# MK_0_4.net
KiCad netlist of a schematic drawn in Altium Designer
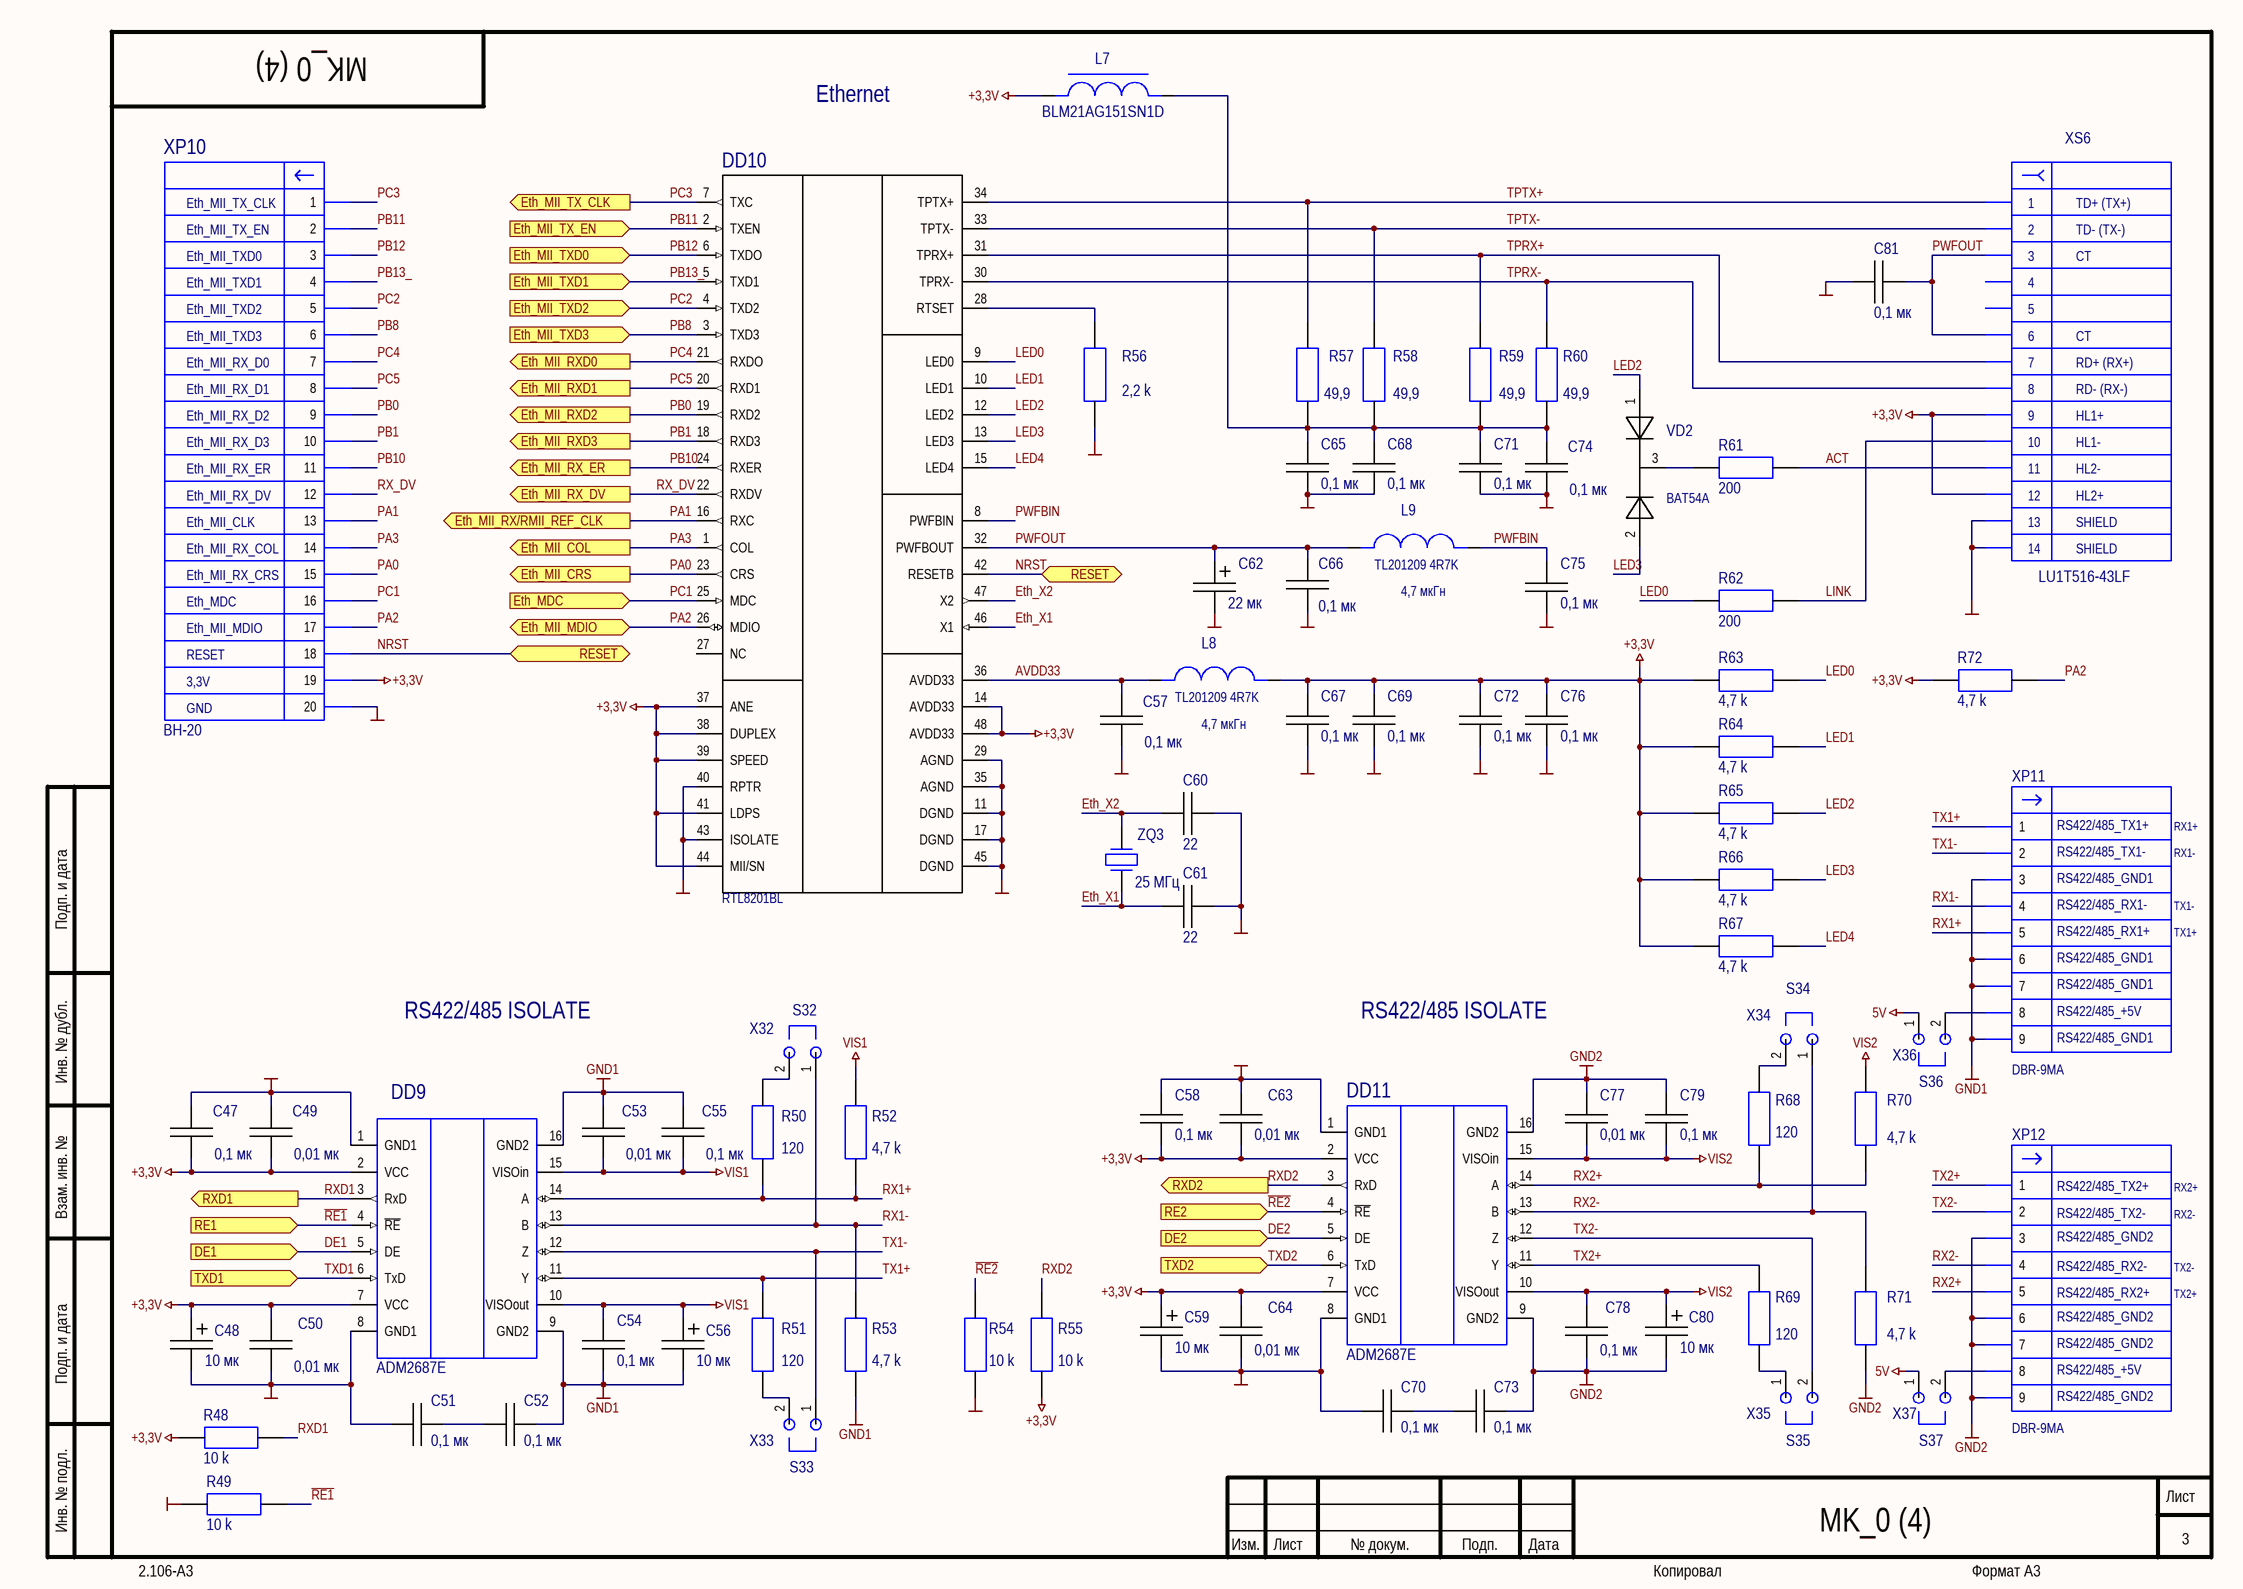
[diagram p0: MK_0 (4).SchDoc]

(export (version "E")
  (design (tool "Eeschema 10.0.6"))
  (components
    (comp (ref "C47")
      (value "0,1 мк")
      (footprint "CAPC_1206")
      (description "Capasitor")
      (fields (field (name "PART NUMBER") "C"))
      (libsource (lib "RLC_GOST") (part "C"))
    )
    (comp (ref "C48")
      (value "10 мк")
      (footprint "3216")
      (description "Capasitor_polar")
      (fields (field (name "PART NUMBER") "CapPol"))
      (libsource (lib "RLC_GOST") (part "CapPol"))
    )
    (comp (ref "C49")
      (value "0,01 мк")
      (footprint "CAPC_1206")
      (description "Capasitor")
      (fields (field (name "PART NUMBER") "C"))
      (libsource (lib "RLC_GOST") (part "C"))
    )
    (comp (ref "C50")
      (value "0,01 мк")
      (footprint "CAPC_1206")
      (description "Capasitor")
      (fields (field (name "PART NUMBER") "C"))
      (libsource (lib "RLC_GOST") (part "C"))
    )
    (comp (ref "C51")
      (value "0,1 мк")
      (footprint "CAPC_1206")
      (description "Capasitor")
      (fields (field (name "PART NUMBER") "C"))
      (libsource (lib "RLC_GOST") (part "C"))
    )
    (comp (ref "C52")
      (value "0,1 мк")
      (footprint "CAPC_1206")
      (description "Capasitor")
      (fields (field (name "PART NUMBER") "C"))
      (libsource (lib "RLC_GOST") (part "C"))
    )
    (comp (ref "C53")
      (value "0,01 мк")
      (footprint "CAPC_1206")
      (description "Capasitor")
      (fields (field (name "PART NUMBER") "C"))
      (libsource (lib "RLC_GOST") (part "C"))
    )
    (comp (ref "C54")
      (value "0,1 мк")
      (footprint "CAPC_1206")
      (description "Capasitor")
      (fields (field (name "PART NUMBER") "C"))
      (libsource (lib "RLC_GOST") (part "C"))
    )
    (comp (ref "C55")
      (value "0,1 мк")
      (footprint "CAPC_1206")
      (description "Capasitor")
      (fields (field (name "PART NUMBER") "C"))
      (libsource (lib "RLC_GOST") (part "C"))
    )
    (comp (ref "C56")
      (value "10 мк")
      (footprint "3216")
      (description "Capasitor_polar")
      (fields (field (name "PART NUMBER") "CapPol"))
      (libsource (lib "RLC_GOST") (part "CapPol"))
    )
    (comp (ref "C57")
      (value "0,1 мк")
      (footprint "CAPC_1206")
      (description "Capasitor")
      (fields (field (name "PART NUMBER") "C"))
      (libsource (lib "RLC_GOST") (part "C"))
    )
    (comp (ref "C58")
      (value "0,1 мк")
      (footprint "CAPC_1206")
      (description "Capasitor")
      (fields (field (name "PART NUMBER") "C"))
      (libsource (lib "RLC_GOST") (part "C"))
    )
    (comp (ref "C59")
      (value "10 мк")
      (footprint "3216")
      (description "Capasitor_polar")
      (fields (field (name "PART NUMBER") "CapPol"))
      (libsource (lib "RLC_GOST") (part "CapPol"))
    )
    (comp (ref "C60")
      (value "22")
      (footprint "CAPC_1206")
      (description "Capasitor")
      (libsource (lib "RLC_GOST") (part "C"))
    )
    (comp (ref "C61")
      (value "22")
      (footprint "CAPC_1206")
      (description "Capasitor")
      (libsource (lib "RLC_GOST") (part "C"))
    )
    (comp (ref "C62")
      (value "22 мк")
      (footprint "3216")
      (description "Capasitor_polar")
      (fields (field (name "PART NUMBER") "CapPol"))
      (libsource (lib "RLC_GOST") (part "CapPol"))
    )
    (comp (ref "C63")
      (value "0,01 мк")
      (footprint "CAPC_1206")
      (description "Capasitor")
      (fields (field (name "PART NUMBER") "C"))
      (libsource (lib "RLC_GOST") (part "C"))
    )
    (comp (ref "C64")
      (value "0,01 мк")
      (footprint "CAPC_1206")
      (description "Capasitor")
      (fields (field (name "PART NUMBER") "C"))
      (libsource (lib "RLC_GOST") (part "C"))
    )
    (comp (ref "C65")
      (value "0,1 мк")
      (footprint "CAPC_1206")
      (description "Capasitor")
      (fields (field (name "PART NUMBER") "C"))
      (libsource (lib "RLC_GOST") (part "C"))
    )
    (comp (ref "C66")
      (value "0,1 мк")
      (footprint "CAPC_1206")
      (description "Capasitor")
      (fields (field (name "PART NUMBER") "C"))
      (libsource (lib "RLC_GOST") (part "C"))
    )
    (comp (ref "C67")
      (value "0,1 мк")
      (footprint "CAPC_1206")
      (description "Capasitor")
      (fields (field (name "PART NUMBER") "C"))
      (libsource (lib "RLC_GOST") (part "C"))
    )
    (comp (ref "C68")
      (value "0,1 мк")
      (footprint "CAPC_1206")
      (description "Capasitor")
      (fields (field (name "PART NUMBER") "C"))
      (libsource (lib "RLC_GOST") (part "C"))
    )
    (comp (ref "C69")
      (value "0,1 мк")
      (footprint "CAPC_1206")
      (description "Capasitor")
      (fields (field (name "PART NUMBER") "C"))
      (libsource (lib "RLC_GOST") (part "C"))
    )
    (comp (ref "C70")
      (value "0,1 мк")
      (footprint "CAPC_1206")
      (description "Capasitor")
      (fields (field (name "PART NUMBER") "C"))
      (libsource (lib "RLC_GOST") (part "C"))
    )
    (comp (ref "C71")
      (value "0,1 мк")
      (footprint "CAPC_1206")
      (description "Capasitor")
      (fields (field (name "PART NUMBER") "C"))
      (libsource (lib "RLC_GOST") (part "C"))
    )
    (comp (ref "C72")
      (value "0,1 мк")
      (footprint "CAPC_1206")
      (description "Capasitor")
      (fields (field (name "PART NUMBER") "C"))
      (libsource (lib "RLC_GOST") (part "C"))
    )
    (comp (ref "C73")
      (value "0,1 мк")
      (footprint "CAPC_1206")
      (description "Capasitor")
      (fields (field (name "PART NUMBER") "C"))
      (libsource (lib "RLC_GOST") (part "C"))
    )
    (comp (ref "C74")
      (value "0,1 мк")
      (footprint "CAPC_1206")
      (description "Capasitor")
      (fields (field (name "PART NUMBER") "C"))
      (libsource (lib "RLC_GOST") (part "C"))
    )
    (comp (ref "C75")
      (value "0,1 мк")
      (footprint "CAPC_1206")
      (description "Capasitor")
      (fields (field (name "PART NUMBER") "C"))
      (libsource (lib "RLC_GOST") (part "C"))
    )
    (comp (ref "C76")
      (value "0,1 мк")
      (footprint "CAPC_1206")
      (description "Capasitor")
      (fields (field (name "PART NUMBER") "C"))
      (libsource (lib "RLC_GOST") (part "C"))
    )
    (comp (ref "C77")
      (value "0,01 мк")
      (footprint "CAPC_1206")
      (description "Capasitor")
      (fields (field (name "PART NUMBER") "C"))
      (libsource (lib "RLC_GOST") (part "C"))
    )
    (comp (ref "C78")
      (value "0,1 мк")
      (footprint "CAPC_1206")
      (description "Capasitor")
      (fields (field (name "PART NUMBER") "C"))
      (libsource (lib "RLC_GOST") (part "C"))
    )
    (comp (ref "C79")
      (value "0,1 мк")
      (footprint "CAPC_1206")
      (description "Capasitor")
      (fields (field (name "PART NUMBER") "C"))
      (libsource (lib "RLC_GOST") (part "C"))
    )
    (comp (ref "C80")
      (value "10 мк")
      (footprint "3216")
      (description "Capasitor_polar")
      (fields (field (name "PART NUMBER") "CapPol"))
      (libsource (lib "RLC_GOST") (part "CapPol"))
    )
    (comp (ref "C81")
      (value "0,1 мк")
      (footprint "CAPC_1206")
      (description "Capasitor")
      (fields (field (name "PART NUMBER") "C"))
      (libsource (lib "RLC_GOST") (part "C"))
    )
    (comp (ref "DD9")
      (value "ADM2687E")
      (footprint "SOIC_IC16")
      (description "RS422/RS485 transceivier 15 kV ESD Protection")
      (libsource (lib "Communication transceiver") (part "ADM2682E"))
    )
    (comp (ref "DD10")
      (value "RTL8201BL")
      (footprint "SQFP48")
      (description "Ethernet phyciever, 10/100M")
      (libsource (lib "Ethernet") (part "RTL8201BL"))
    )
    (comp (ref "DD11")
      (value "ADM2687E")
      (footprint "SOIC_IC16")
      (description "RS422/RS485 transceivier 15 kV ESD Protection")
      (libsource (lib "Communication transceiver") (part "ADM2682E"))
    )
    (comp (ref "L7")
      (value "BLM21AG151SN1D")
      (footprint "C0805")
      (description "Ferrite bead")
      (libsource (lib "RLC_GOST") (part "B"))
    )
    (comp (ref "L8")
      (value "TL201209 4R7K")
      (footprint "C0805")
      (description "Inductance")
      (fields (field (name "VALUE1") "4,7 мкГн"))
      (libsource (lib "RLC_GOST") (part "L"))
    )
    (comp (ref "L9")
      (value "TL201209 4R7K")
      (footprint "C0805")
      (description "Inductance")
      (fields (field (name "VALUE1") "4,7 мкГн"))
      (libsource (lib "RLC_GOST") (part "L"))
    )
    (comp (ref "R48")
      (value "10 k")
      (footprint "SMD_1206")
      (description "Resistor,2 Pin")
      (libsource (lib "RLC_GOST") (part "R_Gost"))
    )
    (comp (ref "R49")
      (value "10 k")
      (footprint "SMD_1206")
      (description "Resistor,2 Pin")
      (libsource (lib "RLC_GOST") (part "R_Gost"))
    )
    (comp (ref "R50")
      (value "120")
      (footprint "SMD_1206")
      (description "Resistor,2 Pin")
      (libsource (lib "RLC_GOST") (part "R_Gost"))
    )
    (comp (ref "R51")
      (value "120")
      (footprint "SMD_1206")
      (description "Resistor,2 Pin")
      (libsource (lib "RLC_GOST") (part "R_Gost"))
    )
    (comp (ref "R52")
      (value "4,7 k")
      (footprint "SMD_1206")
      (description "Resistor,2 Pin")
      (libsource (lib "RLC_GOST") (part "R_Gost"))
    )
    (comp (ref "R53")
      (value "4,7 k")
      (footprint "SMD_1206")
      (description "Resistor,2 Pin")
      (libsource (lib "RLC_GOST") (part "R_Gost"))
    )
    (comp (ref "R54")
      (value "10 k")
      (footprint "SMD_1206")
      (description "Resistor,2 Pin")
      (libsource (lib "RLC_GOST") (part "R_Gost"))
    )
    (comp (ref "R55")
      (value "10 k")
      (footprint "SMD_1206")
      (description "Resistor,2 Pin")
      (libsource (lib "RLC_GOST") (part "R_Gost"))
    )
    (comp (ref "R56")
      (value "2,2 k")
      (footprint "SMD_1206")
      (description "Resistor,2 Pin")
      (libsource (lib "RLC_GOST") (part "R_Gost"))
    )
    (comp (ref "R57")
      (value "49,9")
      (footprint "SMD_1206")
      (description "Resistor,2 Pin")
      (libsource (lib "RLC_GOST") (part "R_Gost"))
    )
    (comp (ref "R58")
      (value "49,9")
      (footprint "SMD_1206")
      (description "Resistor,2 Pin")
      (libsource (lib "RLC_GOST") (part "R_Gost"))
    )
    (comp (ref "R59")
      (value "49,9")
      (footprint "SMD_1206")
      (description "Resistor,2 Pin")
      (libsource (lib "RLC_GOST") (part "R_Gost"))
    )
    (comp (ref "R60")
      (value "49,9")
      (footprint "SMD_1206")
      (description "Resistor,2 Pin")
      (libsource (lib "RLC_GOST") (part "R_Gost"))
    )
    (comp (ref "R61")
      (value "200")
      (footprint "SMD_1206")
      (description "Resistor,2 Pin")
      (libsource (lib "RLC_GOST") (part "R_Gost"))
    )
    (comp (ref "R62")
      (value "200")
      (footprint "SMD_1206")
      (description "Resistor,2 Pin")
      (libsource (lib "RLC_GOST") (part "R_Gost"))
    )
    (comp (ref "R63")
      (value "4,7 k")
      (footprint "SMD_1206")
      (description "Resistor,2 Pin")
      (libsource (lib "RLC_GOST") (part "R_Gost"))
    )
    (comp (ref "R64")
      (value "4,7 k")
      (footprint "SMD_1206")
      (description "Resistor,2 Pin")
      (libsource (lib "RLC_GOST") (part "R_Gost"))
    )
    (comp (ref "R65")
      (value "4,7 k")
      (footprint "SMD_1206")
      (description "Resistor,2 Pin")
      (libsource (lib "RLC_GOST") (part "R_Gost"))
    )
    (comp (ref "R66")
      (value "4,7 k")
      (footprint "SMD_1206")
      (description "Resistor,2 Pin")
      (libsource (lib "RLC_GOST") (part "R_Gost"))
    )
    (comp (ref "R67")
      (value "4,7 k")
      (footprint "SMD_1206")
      (description "Resistor,2 Pin")
      (libsource (lib "RLC_GOST") (part "R_Gost"))
    )
    (comp (ref "R68")
      (value "120")
      (footprint "SMD_1206")
      (description "Resistor,2 Pin")
      (libsource (lib "RLC_GOST") (part "R_Gost"))
    )
    (comp (ref "R69")
      (value "120")
      (footprint "SMD_1206")
      (description "Resistor,2 Pin")
      (libsource (lib "RLC_GOST") (part "R_Gost"))
    )
    (comp (ref "R70")
      (value "4,7 k")
      (footprint "SMD_1206")
      (description "Resistor,2 Pin")
      (libsource (lib "RLC_GOST") (part "R_Gost"))
    )
    (comp (ref "R71")
      (value "4,7 k")
      (footprint "SMD_1206")
      (description "Resistor,2 Pin")
      (libsource (lib "RLC_GOST") (part "R_Gost"))
    )
    (comp (ref "R72")
      (value "4,7 k")
      (footprint "SMD_1206")
      (description "Resistor,2 Pin")
      (libsource (lib "RLC_GOST") (part "R_Gost"))
    )
    (comp (ref "VD2")
      (value "BAT54A")
      (footprint "SOT23")
      (description "Diod Schottky, 3 pin")
      (fields (field (name "MANUFACTURER") "Fairchild"))
      (libsource (lib "Diod") (part "BS40-06"))
    )
    (comp (ref "X32")
      (value "PLS-02")
      (footprint "PLS-2")
      (fields (field (name "JAMPER") "S32"))
      (libsource (lib "Connectors") (part "J2"))
    )
    (comp (ref "X33")
      (value "PLS-02")
      (footprint "PLS-2")
      (fields (field (name "JAMPER") "S33"))
      (libsource (lib "Connectors") (part "J2"))
    )
    (comp (ref "X34")
      (value "PLS-02")
      (footprint "PLS-2")
      (fields (field (name "JAMPER") "S34"))
      (libsource (lib "Connectors") (part "J2"))
    )
    (comp (ref "X35")
      (value "PLS-02")
      (footprint "PLS-2")
      (fields (field (name "JAMPER") "S35"))
      (libsource (lib "Connectors") (part "J2"))
    )
    (comp (ref "X36")
      (value "PLS-02")
      (footprint "PLS-2")
      (fields (field (name "JAMPER") "S36"))
      (libsource (lib "Connectors") (part "J2"))
    )
    (comp (ref "X37")
      (value "PLS-02")
      (footprint "PLS-2")
      (fields (field (name "JAMPER") "S37"))
      (libsource (lib "Connectors") (part "J2"))
    )
    (comp (ref "XP10") (value "BH-20") (footprint "PLD-20") (libsource (lib "Connectors") (part "BH-20")))
    (comp (ref "XP11")
      (value "DBR-9MA")
      (footprint "DB9M")
      (description "X9")
      (fields (field (name "MANUFACTURER") "Ningbo"))
      (libsource (lib "Connectors") (part "X9"))
    )
    (comp (ref "XP12")
      (value "DBR-9MA")
      (footprint "DB9M")
      (description "X9")
      (fields (field (name "MANUFACTURER") "Ningbo"))
      (libsource (lib "Connectors") (part "X9"))
    )
    (comp (ref "XS6")
      (value "LU1T516-43LF")
      (footprint "LU1T516-43LF")
      (description "RJ45")
      (libsource (lib "Connectors") (part "RJ45"))
    )
    (comp (ref "ZQ3")
      (value "25 МГц")
      (footprint "HC-49U_5mm")
      (description "OSC")
      (libsource (lib "Resonators") (part "OSC"))
    )
  )
  (nets
    (net (code "1") (name "+3,3V") (class "Default")
      (node (ref "C47") (pin "1") (pinfunction "1_1") (pintype "passive"))
      (node (ref "C48") (pin "1") (pinfunction "+_1") (pintype "passive"))
      (node (ref "C49") (pin "1") (pinfunction "1_1") (pintype "passive"))
      (node (ref "C50") (pin "2") (pinfunction "2_2") (pintype "passive"))
      (node (ref "C58") (pin "1") (pinfunction "1_1") (pintype "passive"))
      (node (ref "C59") (pin "1") (pinfunction "+_1") (pintype "passive"))
      (node (ref "C63") (pin "1") (pinfunction "1_1") (pintype "passive"))
      (node (ref "C64") (pin "2") (pinfunction "2_2") (pintype "passive"))
      (node (ref "C67") (pin "2") (pinfunction "2_2") (pintype "passive"))
      (node (ref "C69") (pin "2") (pinfunction "2_2") (pintype "passive"))
      (node (ref "C72") (pin "2") (pinfunction "2_2") (pintype "passive"))
      (node (ref "C76") (pin "2") (pinfunction "2_2") (pintype "passive"))
      (node (ref "DD10") (pin "14") (pinfunction "AVDD33_14") (pintype "power_in"))
      (node (ref "DD10") (pin "37") (pinfunction "ANE_37") (pintype "passive"))
      (node (ref "DD10") (pin "38") (pinfunction "DUPLEX_38") (pintype "passive"))
      (node (ref "DD10") (pin "39") (pinfunction "SPEED_39") (pintype "passive"))
      (node (ref "DD10") (pin "41") (pinfunction "LDPS_41") (pintype "passive"))
      (node (ref "DD10") (pin "44") (pinfunction "MII/SN_44") (pintype "passive"))
      (node (ref "DD10") (pin "48") (pinfunction "AVDD33_48") (pintype "power_in"))
      (node (ref "DD11") (pin "2") (pinfunction "VCC_2") (pintype "power_in"))
      (node (ref "DD11") (pin "7") (pinfunction "VCC_7") (pintype "power_in"))
      (node (ref "DD9") (pin "2") (pinfunction "VCC_2") (pintype "power_in"))
      (node (ref "DD9") (pin "7") (pinfunction "VCC_7") (pintype "power_in"))
      (node (ref "L7") (pin "1") (pinfunction "1_1") (pintype "passive"))
      (node (ref "L8") (pin "2") (pinfunction "2_2") (pintype "passive"))
      (node (ref "R48") (pin "1") (pinfunction "1_1") (pintype "passive"))
      (node (ref "R55") (pin "1") (pinfunction "1_1") (pintype "passive"))
      (node (ref "R63") (pin "1") (pinfunction "1_1") (pintype "passive"))
      (node (ref "R64") (pin "1") (pinfunction "1_1") (pintype "passive"))
      (node (ref "R65") (pin "1") (pinfunction "1_1") (pintype "passive"))
      (node (ref "R66") (pin "1") (pinfunction "1_1") (pintype "passive"))
      (node (ref "R67") (pin "1") (pinfunction "1_1") (pintype "passive"))
      (node (ref "R72") (pin "2") (pinfunction "2_2") (pintype "passive"))
      (node (ref "XP10") (pin "19") (pinfunction "19_19") (pintype "passive"))
      (node (ref "XS6") (pin "12") (pinfunction "12_12") (pintype "passive"))
      (node (ref "XS6") (pin "9") (pinfunction "9_9") (pintype "passive"))
    )
    (net (code "2") (name "/ACT") (class "Default")
      (node (ref "R61") (pin "1") (pinfunction "1_1") (pintype "passive"))
      (node (ref "XS6") (pin "11") (pinfunction "11_11") (pintype "passive"))
    )
    (net (code "3") (name "/AVDD33") (class "Default")
      (node (ref "C57") (pin "2") (pinfunction "2_2") (pintype "passive"))
      (node (ref "DD10") (pin "36") (pinfunction "AVDD33_36") (pintype "power_in"))
      (node (ref "L8") (pin "1") (pinfunction "1_1") (pintype "passive"))
    )
    (net (code "4") (name "/DE1") (class "Default")
      (node (ref "DD9") (pin "5") (pinfunction "DE_5") (pintype "input"))
    )
    (net (code "5") (name "/DE2") (class "Default")
      (node (ref "DD11") (pin "5") (pinfunction "DE_5") (pintype "input"))
    )
    (net (code "6") (name "/Eth_X1") (class "Default")
      (node (ref "C61") (pin "2") (pinfunction "2_2") (pintype "passive"))
      (node (ref "DD10") (pin "46") (pinfunction "X1_46") (pintype "input"))
      (node (ref "ZQ3") (pin "1") (pinfunction "1_1") (pintype "passive"))
    )
    (net (code "7") (name "/Eth_X2") (class "Default")
      (node (ref "C60") (pin "2") (pinfunction "2_2") (pintype "passive"))
      (node (ref "DD10") (pin "47") (pinfunction "X2_47") (pintype "output"))
      (node (ref "ZQ3") (pin "2") (pinfunction "2_2") (pintype "passive"))
    )
    (net (code "8") (name "/LED0") (class "Default")
      (node (ref "DD10") (pin "9") (pinfunction "LED0_9") (pintype "passive"))
      (node (ref "R62") (pin "2") (pinfunction "2_2") (pintype "passive"))
      (node (ref "R63") (pin "2") (pinfunction "2_2") (pintype "passive"))
    )
    (net (code "9") (name "/LED1") (class "Default")
      (node (ref "DD10") (pin "10") (pinfunction "LED1_10") (pintype "passive"))
      (node (ref "R64") (pin "2") (pinfunction "2_2") (pintype "passive"))
    )
    (net (code "10") (name "/LED2") (class "Default")
      (node (ref "DD10") (pin "12") (pinfunction "LED2_12") (pintype "passive"))
      (node (ref "R65") (pin "2") (pinfunction "2_2") (pintype "passive"))
      (node (ref "VD2") (pin "1") (pinfunction "+_1") (pintype "passive"))
    )
    (net (code "11") (name "/LED3") (class "Default")
      (node (ref "DD10") (pin "13") (pinfunction "LED3_13") (pintype "passive"))
      (node (ref "R66") (pin "2") (pinfunction "2_2") (pintype "passive"))
      (node (ref "VD2") (pin "2") (pinfunction "-_2") (pintype "passive"))
    )
    (net (code "12") (name "/LED4") (class "Default")
      (node (ref "DD10") (pin "15") (pinfunction "LED4_15") (pintype "passive"))
      (node (ref "R67") (pin "2") (pinfunction "2_2") (pintype "passive"))
    )
    (net (code "13") (name "/LINK") (class "Default")
      (node (ref "R62") (pin "1") (pinfunction "1_1") (pintype "passive"))
      (node (ref "XS6") (pin "10") (pinfunction "10_10") (pintype "passive"))
    )
    (net (code "14") (name "/NRST") (class "Default")
      (node (ref "DD10") (pin "42") (pinfunction "RESETB_42") (pintype "passive"))
      (node (ref "XP10") (pin "18") (pinfunction "18_18") (pintype "passive"))
    )
    (net (code "15") (name "/PA0") (class "Default")
      (node (ref "DD10") (pin "23") (pinfunction "CRS_23") (pintype "output"))
      (node (ref "XP10") (pin "15") (pinfunction "15_15") (pintype "passive"))
    )
    (net (code "16") (name "/PA1") (class "Default")
      (node (ref "DD10") (pin "16") (pinfunction "RXC_16") (pintype "output"))
      (node (ref "XP10") (pin "13") (pinfunction "13_13") (pintype "passive"))
    )
    (net (code "17") (name "/PA2") (class "Default")
      (node (ref "DD10") (pin "26") (pinfunction "MDIO_26") (pintype "bidirectional"))
      (node (ref "R72") (pin "1") (pinfunction "1_1") (pintype "passive"))
      (node (ref "XP10") (pin "17") (pinfunction "17_17") (pintype "passive"))
    )
    (net (code "18") (name "/PA3") (class "Default")
      (node (ref "DD10") (pin "1") (pinfunction "COL_1") (pintype "output"))
      (node (ref "XP10") (pin "14") (pinfunction "14_14") (pintype "passive"))
    )
    (net (code "19") (name "/PB0") (class "Default")
      (node (ref "DD10") (pin "19") (pinfunction "RXD2_19") (pintype "output"))
      (node (ref "XP10") (pin "9") (pinfunction "9_9") (pintype "passive"))
    )
    (net (code "20") (name "/PB1") (class "Default")
      (node (ref "DD10") (pin "18") (pinfunction "RXD3_18") (pintype "output"))
      (node (ref "XP10") (pin "10") (pinfunction "10_10") (pintype "passive"))
    )
    (net (code "21") (name "/PB8") (class "Default")
      (node (ref "DD10") (pin "3") (pinfunction "TXD3_3") (pintype "input"))
      (node (ref "XP10") (pin "6") (pinfunction "6_6") (pintype "passive"))
    )
    (net (code "22") (name "/PB10") (class "Default")
      (node (ref "DD10") (pin "24") (pinfunction "RXER_24") (pintype "output"))
      (node (ref "XP10") (pin "11") (pinfunction "11_11") (pintype "passive"))
    )
    (net (code "23") (name "/PB11") (class "Default")
      (node (ref "DD10") (pin "2") (pinfunction "TXEN_2") (pintype "input"))
      (node (ref "XP10") (pin "2") (pinfunction "2_2") (pintype "passive"))
    )
    (net (code "24") (name "/PB12") (class "Default")
      (node (ref "DD10") (pin "6") (pinfunction "TXDO_6") (pintype "input"))
      (node (ref "XP10") (pin "3") (pinfunction "3_3") (pintype "passive"))
    )
    (net (code "25") (name "/PB13_") (class "Default")
      (node (ref "DD10") (pin "5") (pinfunction "TXD1_5") (pintype "input"))
      (node (ref "XP10") (pin "4") (pinfunction "4_4") (pintype "passive"))
    )
    (net (code "26") (name "/PC1") (class "Default")
      (node (ref "DD10") (pin "25") (pinfunction "MDC_25") (pintype "input"))
      (node (ref "XP10") (pin "16") (pinfunction "16_16") (pintype "passive"))
    )
    (net (code "27") (name "/PC2") (class "Default")
      (node (ref "DD10") (pin "4") (pinfunction "TXD2_4") (pintype "input"))
      (node (ref "XP10") (pin "5") (pinfunction "5_5") (pintype "passive"))
    )
    (net (code "28") (name "/PC3") (class "Default")
      (node (ref "DD10") (pin "7") (pinfunction "TXC_7") (pintype "output"))
      (node (ref "XP10") (pin "1") (pinfunction "1_1") (pintype "passive"))
    )
    (net (code "29") (name "/PC4") (class "Default")
      (node (ref "DD10") (pin "21") (pinfunction "RXDO_21") (pintype "output"))
      (node (ref "XP10") (pin "7") (pinfunction "7_7") (pintype "passive"))
    )
    (net (code "30") (name "/PC5") (class "Default")
      (node (ref "DD10") (pin "20") (pinfunction "RXD1_20") (pintype "output"))
      (node (ref "XP10") (pin "8") (pinfunction "8_8") (pintype "passive"))
    )
    (net (code "31") (name "/PWFBIN") (class "Default")
      (node (ref "C75") (pin "2") (pinfunction "2_2") (pintype "passive"))
      (node (ref "DD10") (pin "8") (pinfunction "PWFBIN_8") (pintype "passive"))
      (node (ref "L9") (pin "2") (pinfunction "2_2") (pintype "passive"))
    )
    (net (code "32") (name "/PWFOUT") (class "Default")
      (node (ref "C62") (pin "1") (pinfunction "+_1") (pintype "passive"))
      (node (ref "C66") (pin "2") (pinfunction "2_2") (pintype "passive"))
      (node (ref "C81") (pin "1") (pinfunction "1_1") (pintype "passive"))
      (node (ref "DD10") (pin "32") (pinfunction "PWFBOUT_32") (pintype "passive"))
      (node (ref "L9") (pin "1") (pinfunction "1_1") (pintype "passive"))
      (node (ref "XS6") (pin "3") (pinfunction "3_3") (pintype "passive"))
      (node (ref "XS6") (pin "6") (pinfunction "6_6") (pintype "passive"))
    )
    (net (code "33") (name "/RE1") (class "Default")
      (node (ref "DD9") (pin "4") (pinfunction "RE_4") (pintype "input"))
      (node (ref "R49") (pin "2") (pinfunction "2_2") (pintype "passive"))
    )
    (net (code "34") (name "/RE2") (class "Default")
      (node (ref "DD11") (pin "4") (pinfunction "RE_4") (pintype "input"))
      (node (ref "R54") (pin "2") (pinfunction "2_2") (pintype "passive"))
    )
    (net (code "35") (name "/RX1+") (class "Default")
      (node (ref "DD9") (pin "14") (pinfunction "A_14") (pintype "bidirectional"))
      (node (ref "R50") (pin "2") (pinfunction "2_2") (pintype "passive"))
      (node (ref "R52") (pin "1") (pinfunction "1_1") (pintype "passive"))
      (node (ref "XP11") (pin "5") (pinfunction "5_5") (pintype "passive"))
    )
    (net (code "36") (name "/RX1-") (class "Default")
      (node (ref "DD9") (pin "13") (pinfunction "B_13") (pintype "bidirectional"))
      (node (ref "R53") (pin "1") (pinfunction "1_1") (pintype "passive"))
      (node (ref "X32") (pin "1") (pinfunction "1_1") (pintype "passive"))
      (node (ref "XP11") (pin "4") (pinfunction "4_4") (pintype "passive"))
    )
    (net (code "37") (name "/RX2+") (class "Default")
      (node (ref "DD11") (pin "14") (pinfunction "A_14") (pintype "bidirectional"))
      (node (ref "R68") (pin "2") (pinfunction "2_2") (pintype "passive"))
      (node (ref "R70") (pin "1") (pinfunction "1_1") (pintype "passive"))
      (node (ref "XP12") (pin "5") (pinfunction "5_5") (pintype "passive"))
    )
    (net (code "38") (name "/RX2-") (class "Default")
      (node (ref "DD11") (pin "13") (pinfunction "B_13") (pintype "bidirectional"))
      (node (ref "R71") (pin "1") (pinfunction "1_1") (pintype "passive"))
      (node (ref "X34") (pin "1") (pinfunction "1_1") (pintype "passive"))
      (node (ref "XP12") (pin "4") (pinfunction "4_4") (pintype "passive"))
    )
    (net (code "39") (name "/RXD1") (class "Default")
      (node (ref "DD9") (pin "3") (pinfunction "RxD_3") (pintype "output"))
      (node (ref "R48") (pin "2") (pinfunction "2_2") (pintype "passive"))
    )
    (net (code "40") (name "/RXD2") (class "Default")
      (node (ref "DD11") (pin "3") (pinfunction "RxD_3") (pintype "output"))
      (node (ref "R55") (pin "2") (pinfunction "2_2") (pintype "passive"))
    )
    (net (code "41") (name "/RX_DV") (class "Default")
      (node (ref "DD10") (pin "22") (pinfunction "RXDV_22") (pintype "output"))
      (node (ref "XP10") (pin "12") (pinfunction "12_12") (pintype "passive"))
    )
    (net (code "42") (name "/TPRX+") (class "Default")
      (node (ref "DD10") (pin "31") (pinfunction "TPRX+_31") (pintype "passive"))
      (node (ref "R59") (pin "2") (pinfunction "2_2") (pintype "passive"))
      (node (ref "XS6") (pin "7") (pinfunction "7_7") (pintype "passive"))
    )
    (net (code "43") (name "/TPRX-") (class "Default")
      (node (ref "DD10") (pin "30") (pinfunction "TPRX-_30") (pintype "passive"))
      (node (ref "R60") (pin "2") (pinfunction "2_2") (pintype "passive"))
      (node (ref "XS6") (pin "8") (pinfunction "8_8") (pintype "passive"))
    )
    (net (code "44") (name "/TPTX+") (class "Default")
      (node (ref "DD10") (pin "34") (pinfunction "TPTX+_34") (pintype "passive"))
      (node (ref "R57") (pin "2") (pinfunction "2_2") (pintype "passive"))
      (node (ref "XS6") (pin "1") (pinfunction "1_1") (pintype "passive"))
    )
    (net (code "45") (name "/TPTX-") (class "Default")
      (node (ref "DD10") (pin "33") (pinfunction "TPTX-_33") (pintype "passive"))
      (node (ref "R58") (pin "2") (pinfunction "2_2") (pintype "passive"))
      (node (ref "XS6") (pin "2") (pinfunction "2_2") (pintype "passive"))
    )
    (net (code "46") (name "/TX1+") (class "Default")
      (node (ref "DD9") (pin "11") (pinfunction "Y_11") (pintype "bidirectional"))
      (node (ref "R51") (pin "1") (pinfunction "1_1") (pintype "passive"))
      (node (ref "XP11") (pin "1") (pinfunction "1_1") (pintype "passive"))
    )
    (net (code "47") (name "/TX1-") (class "Default")
      (node (ref "DD9") (pin "12") (pinfunction "Z_12") (pintype "bidirectional"))
      (node (ref "X33") (pin "1") (pinfunction "1_1") (pintype "passive"))
      (node (ref "XP11") (pin "2") (pinfunction "2_2") (pintype "passive"))
    )
    (net (code "48") (name "/TX2+") (class "Default")
      (node (ref "DD11") (pin "11") (pinfunction "Y_11") (pintype "bidirectional"))
      (node (ref "R69") (pin "1") (pinfunction "1_1") (pintype "passive"))
      (node (ref "XP12") (pin "1") (pinfunction "1_1") (pintype "passive"))
    )
    (net (code "49") (name "/TX2-") (class "Default")
      (node (ref "DD11") (pin "12") (pinfunction "Z_12") (pintype "bidirectional"))
      (node (ref "X35") (pin "2") (pinfunction "2_2") (pintype "passive"))
      (node (ref "XP12") (pin "2") (pinfunction "2_2") (pintype "passive"))
    )
    (net (code "50") (name "/TXD1") (class "Default")
      (node (ref "DD9") (pin "6") (pinfunction "TxD_6") (pintype "input"))
    )
    (net (code "51") (name "/TXD2") (class "Default")
      (node (ref "DD11") (pin "6") (pinfunction "TxD_6") (pintype "input"))
    )
    (net (code "52") (name "5V") (class "Default")
      (node (ref "X36") (pin "1") (pinfunction "1_1") (pintype "passive"))
      (node (ref "X37") (pin "1") (pinfunction "1_1") (pintype "passive"))
    )
    (net (code "53") (name "GND") (class "Default")
      (node (ref "C47") (pin "2") (pinfunction "2_2") (pintype "passive"))
      (node (ref "C48") (pin "2") (pinfunction "-_2") (pintype "passive"))
      (node (ref "C49") (pin "2") (pinfunction "2_2") (pintype "passive"))
      (node (ref "C50") (pin "1") (pinfunction "1_1") (pintype "passive"))
      (node (ref "C51") (pin "2") (pinfunction "2_2") (pintype "passive"))
      (node (ref "C57") (pin "1") (pinfunction "1_1") (pintype "passive"))
      (node (ref "C58") (pin "2") (pinfunction "2_2") (pintype "passive"))
      (node (ref "C59") (pin "2") (pinfunction "-_2") (pintype "passive"))
      (node (ref "C60") (pin "1") (pinfunction "1_1") (pintype "passive"))
      (node (ref "C61") (pin "1") (pinfunction "1_1") (pintype "passive"))
      (node (ref "C62") (pin "2") (pinfunction "-_2") (pintype "passive"))
      (node (ref "C63") (pin "2") (pinfunction "2_2") (pintype "passive"))
      (node (ref "C64") (pin "1") (pinfunction "1_1") (pintype "passive"))
      (node (ref "C65") (pin "1") (pinfunction "1_1") (pintype "passive"))
      (node (ref "C66") (pin "1") (pinfunction "1_1") (pintype "passive"))
      (node (ref "C67") (pin "1") (pinfunction "1_1") (pintype "passive"))
      (node (ref "C68") (pin "1") (pinfunction "1_1") (pintype "passive"))
      (node (ref "C69") (pin "1") (pinfunction "1_1") (pintype "passive"))
      (node (ref "C70") (pin "2") (pinfunction "2_2") (pintype "passive"))
      (node (ref "C71") (pin "1") (pinfunction "1_1") (pintype "passive"))
      (node (ref "C72") (pin "1") (pinfunction "1_1") (pintype "passive"))
      (node (ref "C74") (pin "1") (pinfunction "1_1") (pintype "passive"))
      (node (ref "C75") (pin "1") (pinfunction "1_1") (pintype "passive"))
      (node (ref "C76") (pin "1") (pinfunction "1_1") (pintype "passive"))
      (node (ref "C81") (pin "2") (pinfunction "2_2") (pintype "passive"))
      (node (ref "DD10") (pin "11") (pinfunction "DGND_11") (pintype "power_in"))
      (node (ref "DD10") (pin "17") (pinfunction "DGND_17") (pintype "power_in"))
      (node (ref "DD10") (pin "29") (pinfunction "AGND_29") (pintype "power_in"))
      (node (ref "DD10") (pin "35") (pinfunction "AGND_35") (pintype "power_in"))
      (node (ref "DD10") (pin "40") (pinfunction "RPTR_40") (pintype "passive"))
      (node (ref "DD10") (pin "43") (pinfunction "ISOLATE_43") (pintype "passive"))
      (node (ref "DD10") (pin "45") (pinfunction "DGND_45") (pintype "power_in"))
      (node (ref "DD11") (pin "1") (pinfunction "GND1_1") (pintype "power_in"))
      (node (ref "DD11") (pin "8") (pinfunction "GND1_8") (pintype "power_in"))
      (node (ref "DD9") (pin "1") (pinfunction "GND1_1") (pintype "power_in"))
      (node (ref "DD9") (pin "8") (pinfunction "GND1_8") (pintype "power_in"))
      (node (ref "R49") (pin "1") (pinfunction "1_1") (pintype "passive"))
      (node (ref "R54") (pin "1") (pinfunction "1_1") (pintype "passive"))
      (node (ref "R56") (pin "1") (pinfunction "1_1") (pintype "passive"))
      (node (ref "XP10") (pin "20") (pinfunction "20_20") (pintype "passive"))
      (node (ref "XS6") (pin "13") (pinfunction "13_13") (pintype "passive"))
      (node (ref "XS6") (pin "14") (pinfunction "14_14") (pintype "passive"))
    )
    (net (code "54") (name "GND1") (class "Default")
      (node (ref "C52") (pin "1") (pinfunction "1_1") (pintype "passive"))
      (node (ref "C53") (pin "2") (pinfunction "2_2") (pintype "passive"))
      (node (ref "C54") (pin "1") (pinfunction "1_1") (pintype "passive"))
      (node (ref "C55") (pin "2") (pinfunction "2_2") (pintype "passive"))
      (node (ref "C56") (pin "2") (pinfunction "-_2") (pintype "passive"))
      (node (ref "DD9") (pin "16") (pinfunction "GND2_16") (pintype "power_in"))
      (node (ref "DD9") (pin "9") (pinfunction "GND2_9") (pintype "power_in"))
      (node (ref "R53") (pin "2") (pinfunction "2_2") (pintype "passive"))
      (node (ref "XP11") (pin "3") (pinfunction "3_3") (pintype "passive"))
      (node (ref "XP11") (pin "6") (pinfunction "6_6") (pintype "passive"))
      (node (ref "XP11") (pin "7") (pinfunction "7_7") (pintype "passive"))
      (node (ref "XP11") (pin "9") (pinfunction "9_9") (pintype "passive"))
    )
    (net (code "55") (name "GND2") (class "Default")
      (node (ref "C73") (pin "1") (pinfunction "1_1") (pintype "passive"))
      (node (ref "C77") (pin "2") (pinfunction "2_2") (pintype "passive"))
      (node (ref "C78") (pin "1") (pinfunction "1_1") (pintype "passive"))
      (node (ref "C79") (pin "2") (pinfunction "2_2") (pintype "passive"))
      (node (ref "C80") (pin "2") (pinfunction "-_2") (pintype "passive"))
      (node (ref "DD11") (pin "16") (pinfunction "GND2_16") (pintype "power_in"))
      (node (ref "DD11") (pin "9") (pinfunction "GND2_9") (pintype "power_in"))
      (node (ref "R71") (pin "2") (pinfunction "2_2") (pintype "passive"))
      (node (ref "XP12") (pin "3") (pinfunction "3_3") (pintype "passive"))
      (node (ref "XP12") (pin "6") (pinfunction "6_6") (pintype "passive"))
      (node (ref "XP12") (pin "7") (pinfunction "7_7") (pintype "passive"))
      (node (ref "XP12") (pin "9") (pinfunction "9_9") (pintype "passive"))
    )
    (net (code "56") (name "Net-(C51-Pad1)") (class "Default")
      (node (ref "C51") (pin "1") (pinfunction "1_1") (pintype "passive"))
      (node (ref "C52") (pin "2") (pinfunction "2_2") (pintype "passive"))
    )
    (net (code "57") (name "Net-(C65-Pad2)") (class "Default")
      (node (ref "C65") (pin "2") (pinfunction "2_2") (pintype "passive"))
      (node (ref "C68") (pin "2") (pinfunction "2_2") (pintype "passive"))
      (node (ref "C71") (pin "2") (pinfunction "2_2") (pintype "passive"))
      (node (ref "C74") (pin "2") (pinfunction "2_2") (pintype "passive"))
      (node (ref "L7") (pin "2") (pinfunction "2_2") (pintype "passive"))
      (node (ref "R57") (pin "1") (pinfunction "1_1") (pintype "passive"))
      (node (ref "R58") (pin "1") (pinfunction "1_1") (pintype "passive"))
      (node (ref "R59") (pin "1") (pinfunction "1_1") (pintype "passive"))
      (node (ref "R60") (pin "1") (pinfunction "1_1") (pintype "passive"))
    )
    (net (code "58") (name "Net-(C70-Pad1)") (class "Default")
      (node (ref "C70") (pin "1") (pinfunction "1_1") (pintype "passive"))
      (node (ref "C73") (pin "2") (pinfunction "2_2") (pintype "passive"))
    )
    (net (code "59") (name "Net-(DD10-RTSET)") (class "Default")
      (node (ref "DD10") (pin "28") (pinfunction "RTSET_28") (pintype "passive"))
      (node (ref "R56") (pin "2") (pinfunction "2_2") (pintype "passive"))
    )
    (net (code "60") (name "Net-(R50-Pad1)") (class "Default")
      (node (ref "R50") (pin "1") (pinfunction "1_1") (pintype "passive"))
      (node (ref "X32") (pin "2") (pinfunction "2_2") (pintype "passive"))
    )
    (net (code "61") (name "Net-(R51-Pad2)") (class "Default")
      (node (ref "R51") (pin "2") (pinfunction "2_2") (pintype "passive"))
      (node (ref "X33") (pin "2") (pinfunction "2_2") (pintype "passive"))
    )
    (net (code "62") (name "Net-(R61-Pad2)") (class "Default")
      (node (ref "R61") (pin "2") (pinfunction "2_2") (pintype "passive"))
      (node (ref "VD2") (pin "3") (pintype "passive"))
    )
    (net (code "63") (name "Net-(R68-Pad1)") (class "Default")
      (node (ref "R68") (pin "1") (pinfunction "1_1") (pintype "passive"))
      (node (ref "X34") (pin "2") (pinfunction "2_2") (pintype "passive"))
    )
    (net (code "64") (name "Net-(R69-Pad2)") (class "Default")
      (node (ref "R69") (pin "2") (pinfunction "2_2") (pintype "passive"))
      (node (ref "X35") (pin "1") (pinfunction "1_1") (pintype "passive"))
    )
    (net (code "65") (name "Net-(X36-Pad2)") (class "Default")
      (node (ref "X36") (pin "2") (pinfunction "2_2") (pintype "passive"))
      (node (ref "XP11") (pin "8") (pinfunction "8_8") (pintype "passive"))
    )
    (net (code "66") (name "Net-(X37-Pad2)") (class "Default")
      (node (ref "X37") (pin "2") (pinfunction "2_2") (pintype "passive"))
      (node (ref "XP12") (pin "8") (pinfunction "8_8") (pintype "passive"))
    )
    (net (code "67") (name "VIS1") (class "Default")
      (node (ref "C53") (pin "1") (pinfunction "1_1") (pintype "passive"))
      (node (ref "C54") (pin "2") (pinfunction "2_2") (pintype "passive"))
      (node (ref "C55") (pin "1") (pinfunction "1_1") (pintype "passive"))
      (node (ref "C56") (pin "1") (pinfunction "+_1") (pintype "passive"))
      (node (ref "DD9") (pin "10") (pinfunction "VISOout_10") (pintype "power_in"))
      (node (ref "DD9") (pin "15") (pinfunction "VISOin_15") (pintype "power_in"))
      (node (ref "R52") (pin "2") (pinfunction "2_2") (pintype "passive"))
    )
    (net (code "68") (name "VIS2") (class "Default")
      (node (ref "C77") (pin "1") (pinfunction "1_1") (pintype "passive"))
      (node (ref "C78") (pin "2") (pinfunction "2_2") (pintype "passive"))
      (node (ref "C79") (pin "1") (pinfunction "1_1") (pintype "passive"))
      (node (ref "C80") (pin "1") (pinfunction "+_1") (pintype "passive"))
      (node (ref "DD11") (pin "10") (pinfunction "VISOout_10") (pintype "power_in"))
      (node (ref "DD11") (pin "15") (pinfunction "VISOin_15") (pintype "power_in"))
      (node (ref "R70") (pin "2") (pinfunction "2_2") (pintype "passive"))
    )
    (net (code "69") (name "unconnected-(DD10-NC-Pad27)") (class "Default")
      (node (ref "DD10") (pin "27") (pinfunction "NC_27") (pintype "passive"))
    )
    (net (code "70") (name "unconnected-(XS6-Pad4)") (class "Default")
      (node (ref "XS6") (pin "4") (pinfunction "4_4") (pintype "passive"))
    )
    (net (code "71") (name "unconnected-(XS6-Pad5)") (class "Default")
      (node (ref "XS6") (pin "5") (pinfunction "5_5") (pintype "passive"))
    )
  )
)
